# UmnitsaRGB.net
KiCad netlist of a schematic drawn in EAGLE
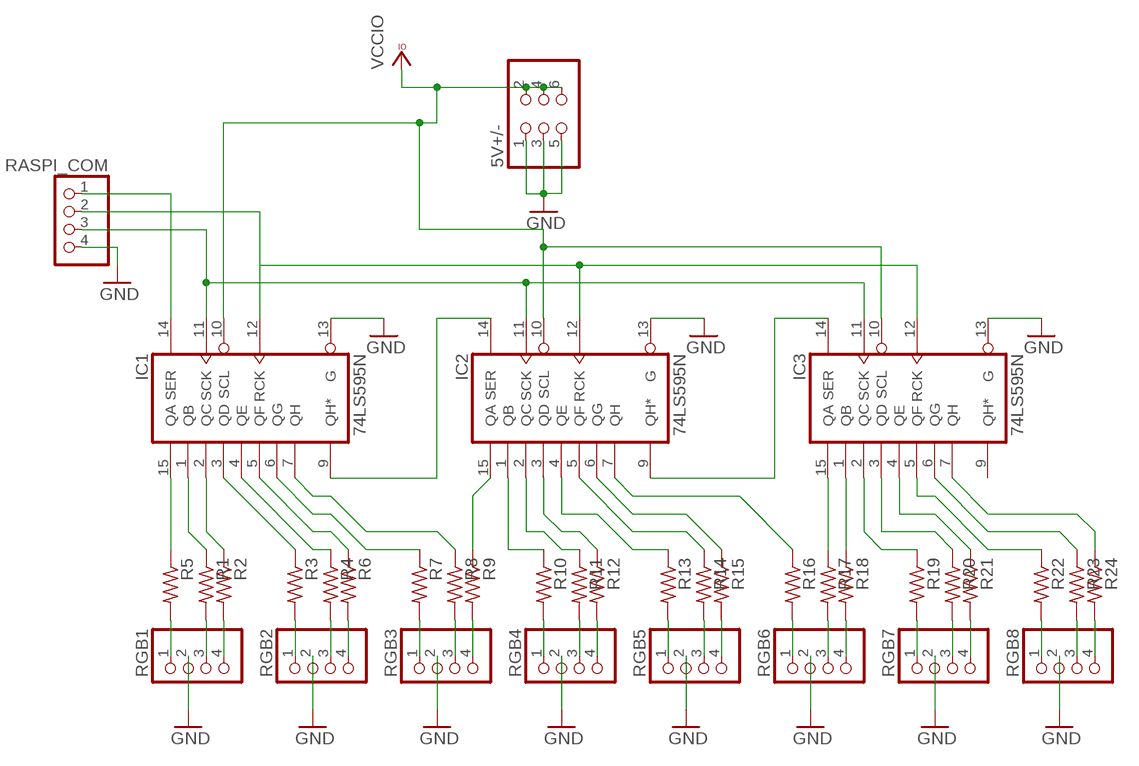
[diagram p0: schematic, sheet 1]

(export (version "E")
  (design (tool "Eeschema 10.0.6"))
  (components
    (comp (ref "5V+/-")
      (value "PINHD-2X3")
      (footprint "eagle-import:2X03")
      (libsource (lib "eagle-import") (part "PINHD-2X3"))
    )
    (comp (ref "IC1")
      (value "74LS595N")
      (footprint "eagle-import:DIL16")
      (libsource (lib "eagle-import") (part "74595NLS"))
    )
    (comp (ref "IC2")
      (value "74LS595N")
      (footprint "eagle-import:DIL16")
      (libsource (lib "eagle-import") (part "74595NLS"))
    )
    (comp (ref "IC3")
      (value "74LS595N")
      (footprint "eagle-import:DIL16")
      (libsource (lib "eagle-import") (part "74595NLS"))
    )
    (comp (ref "R1")
      (value "R-US_0204/7")
      (footprint "eagle-import:0204_7")
      (libsource (lib "eagle-import") (part "R-US_0204/7"))
    )
    (comp (ref "R2")
      (value "R-US_0204/7")
      (footprint "eagle-import:0204_7")
      (libsource (lib "eagle-import") (part "R-US_0204/7"))
    )
    (comp (ref "R3")
      (value "R-US_0204/7")
      (footprint "eagle-import:0204_7")
      (libsource (lib "eagle-import") (part "R-US_0204/7"))
    )
    (comp (ref "R4")
      (value "R-US_0204/7")
      (footprint "eagle-import:0204_7")
      (libsource (lib "eagle-import") (part "R-US_0204/7"))
    )
    (comp (ref "R5")
      (value "R-US_0204/7")
      (footprint "eagle-import:0204_7")
      (libsource (lib "eagle-import") (part "R-US_0204/7"))
    )
    (comp (ref "R6")
      (value "R-US_0204/7")
      (footprint "eagle-import:0204_7")
      (libsource (lib "eagle-import") (part "R-US_0204/7"))
    )
    (comp (ref "R7")
      (value "R-US_0204/7")
      (footprint "eagle-import:0204_7")
      (libsource (lib "eagle-import") (part "R-US_0204/7"))
    )
    (comp (ref "R8")
      (value "R-US_0204/7")
      (footprint "eagle-import:0204_7")
      (libsource (lib "eagle-import") (part "R-US_0204/7"))
    )
    (comp (ref "R9")
      (value "R-US_0204/7")
      (footprint "eagle-import:0204_7")
      (libsource (lib "eagle-import") (part "R-US_0204/7"))
    )
    (comp (ref "R10")
      (value "R-US_0204/7")
      (footprint "eagle-import:0204_7")
      (libsource (lib "eagle-import") (part "R-US_0204/7"))
    )
    (comp (ref "R11")
      (value "R-US_0204/7")
      (footprint "eagle-import:0204_7")
      (libsource (lib "eagle-import") (part "R-US_0204/7"))
    )
    (comp (ref "R12")
      (value "R-US_0204/7")
      (footprint "eagle-import:0204_7")
      (libsource (lib "eagle-import") (part "R-US_0204/7"))
    )
    (comp (ref "R13")
      (value "R-US_0204/7")
      (footprint "eagle-import:0204_7")
      (libsource (lib "eagle-import") (part "R-US_0204/7"))
    )
    (comp (ref "R14")
      (value "R-US_0204/7")
      (footprint "eagle-import:0204_7")
      (libsource (lib "eagle-import") (part "R-US_0204/7"))
    )
    (comp (ref "R15")
      (value "R-US_0204/7")
      (footprint "eagle-import:0204_7")
      (libsource (lib "eagle-import") (part "R-US_0204/7"))
    )
    (comp (ref "R16")
      (value "R-US_0204/7")
      (footprint "eagle-import:0204_7")
      (libsource (lib "eagle-import") (part "R-US_0204/7"))
    )
    (comp (ref "R17")
      (value "R-US_0204/7")
      (footprint "eagle-import:0204_7")
      (libsource (lib "eagle-import") (part "R-US_0204/7"))
    )
    (comp (ref "R18")
      (value "R-US_0204/7")
      (footprint "eagle-import:0204_7")
      (libsource (lib "eagle-import") (part "R-US_0204/7"))
    )
    (comp (ref "R19")
      (value "R-US_0204/7")
      (footprint "eagle-import:0204_7")
      (libsource (lib "eagle-import") (part "R-US_0204/7"))
    )
    (comp (ref "R20")
      (value "R-US_0204/7")
      (footprint "eagle-import:0204_7")
      (libsource (lib "eagle-import") (part "R-US_0204/7"))
    )
    (comp (ref "R21")
      (value "R-US_0204/7")
      (footprint "eagle-import:0204_7")
      (libsource (lib "eagle-import") (part "R-US_0204/7"))
    )
    (comp (ref "R22")
      (value "R-US_0204/7")
      (footprint "eagle-import:0204_7")
      (libsource (lib "eagle-import") (part "R-US_0204/7"))
    )
    (comp (ref "R23")
      (value "R-US_0204/7")
      (footprint "eagle-import:0204_7")
      (libsource (lib "eagle-import") (part "R-US_0204/7"))
    )
    (comp (ref "R24")
      (value "R-US_0204/7")
      (footprint "eagle-import:0204_7")
      (libsource (lib "eagle-import") (part "R-US_0204/7"))
    )
    (comp (ref "RASPI_COM")
      (value "PINHD-1X4")
      (footprint "eagle-import:1X04")
      (libsource (lib "eagle-import") (part "PINHD-1X4"))
    )
    (comp (ref "RGB1")
      (value "PINHD-1X4")
      (footprint "eagle-import:1X04")
      (libsource (lib "eagle-import") (part "PINHD-1X4"))
    )
    (comp (ref "RGB2")
      (value "PINHD-1X4")
      (footprint "eagle-import:1X04")
      (libsource (lib "eagle-import") (part "PINHD-1X4"))
    )
    (comp (ref "RGB3")
      (value "PINHD-1X4")
      (footprint "eagle-import:1X04")
      (libsource (lib "eagle-import") (part "PINHD-1X4"))
    )
    (comp (ref "RGB4")
      (value "PINHD-1X4")
      (footprint "eagle-import:1X04")
      (libsource (lib "eagle-import") (part "PINHD-1X4"))
    )
    (comp (ref "RGB5")
      (value "PINHD-1X4")
      (footprint "eagle-import:1X04")
      (libsource (lib "eagle-import") (part "PINHD-1X4"))
    )
    (comp (ref "RGB6")
      (value "PINHD-1X4")
      (footprint "eagle-import:1X04")
      (libsource (lib "eagle-import") (part "PINHD-1X4"))
    )
    (comp (ref "RGB7")
      (value "PINHD-1X4")
      (footprint "eagle-import:1X04")
      (libsource (lib "eagle-import") (part "PINHD-1X4"))
    )
    (comp (ref "RGB8")
      (value "PINHD-1X4")
      (footprint "eagle-import:1X04")
      (libsource (lib "eagle-import") (part "PINHD-1X4"))
    )
  )
  (nets
    (net (code "1") (name "GND") (class "Default")
      (node (ref "5V+/-") (pin "1") (pinfunction "1_1") (pintype "passive"))
      (node (ref "5V+/-") (pin "3") (pinfunction "3_3") (pintype "passive"))
      (node (ref "5V+/-") (pin "5") (pinfunction "5_5") (pintype "passive"))
      (node (ref "IC1") (pin "13") (pinfunction "G_13") (pintype "input"))
      (node (ref "IC2") (pin "13") (pinfunction "G_13") (pintype "input"))
      (node (ref "IC3") (pin "13") (pinfunction "G_13") (pintype "input"))
      (node (ref "RASPI_COM") (pin "4") (pinfunction "4_4") (pintype "passive"))
      (node (ref "RGB1") (pin "2") (pinfunction "2_2") (pintype "passive"))
      (node (ref "RGB2") (pin "2") (pinfunction "2_2") (pintype "passive"))
      (node (ref "RGB3") (pin "2") (pinfunction "2_2") (pintype "passive"))
      (node (ref "RGB4") (pin "2") (pinfunction "2_2") (pintype "passive"))
      (node (ref "RGB5") (pin "2") (pinfunction "2_2") (pintype "passive"))
      (node (ref "RGB6") (pin "2") (pinfunction "2_2") (pintype "passive"))
      (node (ref "RGB7") (pin "2") (pinfunction "2_2") (pintype "passive"))
      (node (ref "RGB8") (pin "2") (pinfunction "2_2") (pintype "passive"))
    )
    (net (code "2") (name "Net-(IC1A-QA)") (class "Default")
      (node (ref "IC1") (pin "15") (pinfunction "QA_15") (pintype "tri_state"))
      (node (ref "R5") (pin "1") (pinfunction "1_1") (pintype "passive"))
    )
    (net (code "3") (name "Net-(IC1A-QB)") (class "Default")
      (node (ref "IC1") (pin "1") (pinfunction "QB_1") (pintype "tri_state"))
      (node (ref "R1") (pin "1") (pinfunction "1_1") (pintype "passive"))
    )
    (net (code "4") (name "Net-(IC1A-QC)") (class "Default")
      (node (ref "IC1") (pin "2") (pinfunction "QC_2") (pintype "tri_state"))
      (node (ref "R2") (pin "1") (pinfunction "1_1") (pintype "passive"))
    )
    (net (code "5") (name "Net-(IC1A-QD)") (class "Default")
      (node (ref "IC1") (pin "3") (pinfunction "QD_3") (pintype "tri_state"))
      (node (ref "R3") (pin "1") (pinfunction "1_1") (pintype "passive"))
    )
    (net (code "6") (name "Net-(IC1A-QE)") (class "Default")
      (node (ref "IC1") (pin "4") (pinfunction "QE_4") (pintype "tri_state"))
      (node (ref "R4") (pin "1") (pinfunction "1_1") (pintype "passive"))
    )
    (net (code "7") (name "Net-(IC1A-QF)") (class "Default")
      (node (ref "IC1") (pin "5") (pinfunction "QF_5") (pintype "tri_state"))
      (node (ref "R6") (pin "1") (pinfunction "1_1") (pintype "passive"))
    )
    (net (code "8") (name "Net-(IC1A-QG)") (class "Default")
      (node (ref "IC1") (pin "6") (pinfunction "QG_6") (pintype "tri_state"))
      (node (ref "R7") (pin "1") (pinfunction "1_1") (pintype "passive"))
    )
    (net (code "9") (name "Net-(IC1A-QH)") (class "Default")
      (node (ref "IC1") (pin "7") (pinfunction "QH_7") (pintype "tri_state"))
      (node (ref "R8") (pin "1") (pinfunction "1_1") (pintype "passive"))
    )
    (net (code "10") (name "Net-(IC1A-QH*)") (class "Default")
      (node (ref "IC1") (pin "9") (pinfunction "QH*_9") (pintype "tri_state"))
      (node (ref "IC2") (pin "14") (pinfunction "SER_14") (pintype "input"))
    )
    (net (code "11") (name "Net-(IC1A-RCK)") (class "Default")
      (node (ref "IC1") (pin "12") (pinfunction "RCK_12") (pintype "input"))
      (node (ref "IC2") (pin "12") (pinfunction "RCK_12") (pintype "input"))
      (node (ref "IC3") (pin "12") (pinfunction "RCK_12") (pintype "input"))
      (node (ref "RASPI_COM") (pin "2") (pinfunction "2_2") (pintype "passive"))
    )
    (net (code "12") (name "Net-(IC1A-SCK)") (class "Default")
      (node (ref "IC1") (pin "11") (pinfunction "SCK_11") (pintype "input"))
      (node (ref "IC2") (pin "11") (pinfunction "SCK_11") (pintype "input"))
      (node (ref "IC3") (pin "11") (pinfunction "SCK_11") (pintype "input"))
      (node (ref "RASPI_COM") (pin "3") (pinfunction "3_3") (pintype "passive"))
    )
    (net (code "13") (name "Net-(IC1A-SER)") (class "Default")
      (node (ref "IC1") (pin "14") (pinfunction "SER_14") (pintype "input"))
      (node (ref "RASPI_COM") (pin "1") (pinfunction "1_1") (pintype "passive"))
    )
    (net (code "14") (name "Net-(IC2A-QA)") (class "Default")
      (node (ref "IC2") (pin "15") (pinfunction "QA_15") (pintype "tri_state"))
      (node (ref "R9") (pin "1") (pinfunction "1_1") (pintype "passive"))
    )
    (net (code "15") (name "Net-(IC2A-QB)") (class "Default")
      (node (ref "IC2") (pin "1") (pinfunction "QB_1") (pintype "tri_state"))
      (node (ref "R10") (pin "1") (pinfunction "1_1") (pintype "passive"))
    )
    (net (code "16") (name "Net-(IC2A-QC)") (class "Default")
      (node (ref "IC2") (pin "2") (pinfunction "QC_2") (pintype "tri_state"))
      (node (ref "R11") (pin "1") (pinfunction "1_1") (pintype "passive"))
    )
    (net (code "17") (name "Net-(IC2A-QD)") (class "Default")
      (node (ref "IC2") (pin "3") (pinfunction "QD_3") (pintype "tri_state"))
      (node (ref "R12") (pin "1") (pinfunction "1_1") (pintype "passive"))
    )
    (net (code "18") (name "Net-(IC2A-QE)") (class "Default")
      (node (ref "IC2") (pin "4") (pinfunction "QE_4") (pintype "tri_state"))
      (node (ref "R13") (pin "1") (pinfunction "1_1") (pintype "passive"))
    )
    (net (code "19") (name "Net-(IC2A-QF)") (class "Default")
      (node (ref "IC2") (pin "5") (pinfunction "QF_5") (pintype "tri_state"))
      (node (ref "R14") (pin "1") (pinfunction "1_1") (pintype "passive"))
    )
    (net (code "20") (name "Net-(IC2A-QG)") (class "Default")
      (node (ref "IC2") (pin "6") (pinfunction "QG_6") (pintype "tri_state"))
      (node (ref "R15") (pin "1") (pinfunction "1_1") (pintype "passive"))
    )
    (net (code "21") (name "Net-(IC2A-QH)") (class "Default")
      (node (ref "IC2") (pin "7") (pinfunction "QH_7") (pintype "tri_state"))
      (node (ref "R16") (pin "1") (pinfunction "1_1") (pintype "passive"))
    )
    (net (code "22") (name "Net-(IC2A-QH*)") (class "Default")
      (node (ref "IC2") (pin "9") (pinfunction "QH*_9") (pintype "tri_state"))
      (node (ref "IC3") (pin "14") (pinfunction "SER_14") (pintype "input"))
    )
    (net (code "23") (name "Net-(IC3A-QA)") (class "Default")
      (node (ref "IC3") (pin "15") (pinfunction "QA_15") (pintype "tri_state"))
      (node (ref "R17") (pin "1") (pinfunction "1_1") (pintype "passive"))
    )
    (net (code "24") (name "Net-(IC3A-QB)") (class "Default")
      (node (ref "IC3") (pin "1") (pinfunction "QB_1") (pintype "tri_state"))
      (node (ref "R18") (pin "1") (pinfunction "1_1") (pintype "passive"))
    )
    (net (code "25") (name "Net-(IC3A-QC)") (class "Default")
      (node (ref "IC3") (pin "2") (pinfunction "QC_2") (pintype "tri_state"))
      (node (ref "R19") (pin "1") (pinfunction "1_1") (pintype "passive"))
    )
    (net (code "26") (name "Net-(IC3A-QD)") (class "Default")
      (node (ref "IC3") (pin "3") (pinfunction "QD_3") (pintype "tri_state"))
      (node (ref "R20") (pin "1") (pinfunction "1_1") (pintype "passive"))
    )
    (net (code "27") (name "Net-(IC3A-QE)") (class "Default")
      (node (ref "IC3") (pin "4") (pinfunction "QE_4") (pintype "tri_state"))
      (node (ref "R21") (pin "1") (pinfunction "1_1") (pintype "passive"))
    )
    (net (code "28") (name "Net-(IC3A-QF)") (class "Default")
      (node (ref "IC3") (pin "5") (pinfunction "QF_5") (pintype "tri_state"))
      (node (ref "R22") (pin "1") (pinfunction "1_1") (pintype "passive"))
    )
    (net (code "29") (name "Net-(IC3A-QG)") (class "Default")
      (node (ref "IC3") (pin "6") (pinfunction "QG_6") (pintype "tri_state"))
      (node (ref "R23") (pin "1") (pinfunction "1_1") (pintype "passive"))
    )
    (net (code "30") (name "Net-(IC3A-QH)") (class "Default")
      (node (ref "IC3") (pin "7") (pinfunction "QH_7") (pintype "tri_state"))
      (node (ref "R24") (pin "1") (pinfunction "1_1") (pintype "passive"))
    )
    (net (code "31") (name "Net-(R1-Pad2)") (class "Default")
      (node (ref "R1") (pin "2") (pinfunction "2_2") (pintype "passive"))
      (node (ref "RGB1") (pin "3") (pinfunction "3_3") (pintype "passive"))
    )
    (net (code "32") (name "Net-(R2-Pad2)") (class "Default")
      (node (ref "R2") (pin "2") (pinfunction "2_2") (pintype "passive"))
      (node (ref "RGB1") (pin "4") (pinfunction "4_4") (pintype "passive"))
    )
    (net (code "33") (name "Net-(R3-Pad2)") (class "Default")
      (node (ref "R3") (pin "2") (pinfunction "2_2") (pintype "passive"))
      (node (ref "RGB2") (pin "1") (pinfunction "1_1") (pintype "passive"))
    )
    (net (code "34") (name "Net-(R4-Pad2)") (class "Default")
      (node (ref "R4") (pin "2") (pinfunction "2_2") (pintype "passive"))
      (node (ref "RGB2") (pin "3") (pinfunction "3_3") (pintype "passive"))
    )
    (net (code "35") (name "Net-(R5-Pad2)") (class "Default")
      (node (ref "R5") (pin "2") (pinfunction "2_2") (pintype "passive"))
      (node (ref "RGB1") (pin "1") (pinfunction "1_1") (pintype "passive"))
    )
    (net (code "36") (name "Net-(R6-Pad2)") (class "Default")
      (node (ref "R6") (pin "2") (pinfunction "2_2") (pintype "passive"))
      (node (ref "RGB2") (pin "4") (pinfunction "4_4") (pintype "passive"))
    )
    (net (code "37") (name "Net-(R7-Pad2)") (class "Default")
      (node (ref "R7") (pin "2") (pinfunction "2_2") (pintype "passive"))
      (node (ref "RGB3") (pin "1") (pinfunction "1_1") (pintype "passive"))
    )
    (net (code "38") (name "Net-(R8-Pad2)") (class "Default")
      (node (ref "R8") (pin "2") (pinfunction "2_2") (pintype "passive"))
      (node (ref "RGB3") (pin "3") (pinfunction "3_3") (pintype "passive"))
    )
    (net (code "39") (name "Net-(R9-Pad2)") (class "Default")
      (node (ref "R9") (pin "2") (pinfunction "2_2") (pintype "passive"))
      (node (ref "RGB3") (pin "4") (pinfunction "4_4") (pintype "passive"))
    )
    (net (code "40") (name "Net-(R10-Pad2)") (class "Default")
      (node (ref "R10") (pin "2") (pinfunction "2_2") (pintype "passive"))
      (node (ref "RGB4") (pin "1") (pinfunction "1_1") (pintype "passive"))
    )
    (net (code "41") (name "Net-(R11-Pad2)") (class "Default")
      (node (ref "R11") (pin "2") (pinfunction "2_2") (pintype "passive"))
      (node (ref "RGB4") (pin "3") (pinfunction "3_3") (pintype "passive"))
    )
    (net (code "42") (name "Net-(R12-Pad2)") (class "Default")
      (node (ref "R12") (pin "2") (pinfunction "2_2") (pintype "passive"))
      (node (ref "RGB4") (pin "4") (pinfunction "4_4") (pintype "passive"))
    )
    (net (code "43") (name "Net-(R13-Pad2)") (class "Default")
      (node (ref "R13") (pin "2") (pinfunction "2_2") (pintype "passive"))
      (node (ref "RGB5") (pin "1") (pinfunction "1_1") (pintype "passive"))
    )
    (net (code "44") (name "Net-(R14-Pad2)") (class "Default")
      (node (ref "R14") (pin "2") (pinfunction "2_2") (pintype "passive"))
      (node (ref "RGB5") (pin "3") (pinfunction "3_3") (pintype "passive"))
    )
    (net (code "45") (name "Net-(R15-Pad2)") (class "Default")
      (node (ref "R15") (pin "2") (pinfunction "2_2") (pintype "passive"))
      (node (ref "RGB5") (pin "4") (pinfunction "4_4") (pintype "passive"))
    )
    (net (code "46") (name "Net-(R16-Pad2)") (class "Default")
      (node (ref "R16") (pin "2") (pinfunction "2_2") (pintype "passive"))
      (node (ref "RGB6") (pin "1") (pinfunction "1_1") (pintype "passive"))
    )
    (net (code "47") (name "Net-(R17-Pad2)") (class "Default")
      (node (ref "R17") (pin "2") (pinfunction "2_2") (pintype "passive"))
      (node (ref "RGB6") (pin "3") (pinfunction "3_3") (pintype "passive"))
    )
    (net (code "48") (name "Net-(R18-Pad2)") (class "Default")
      (node (ref "R18") (pin "2") (pinfunction "2_2") (pintype "passive"))
      (node (ref "RGB6") (pin "4") (pinfunction "4_4") (pintype "passive"))
    )
    (net (code "49") (name "Net-(R19-Pad2)") (class "Default")
      (node (ref "R19") (pin "2") (pinfunction "2_2") (pintype "passive"))
      (node (ref "RGB7") (pin "1") (pinfunction "1_1") (pintype "passive"))
    )
    (net (code "50") (name "Net-(R20-Pad2)") (class "Default")
      (node (ref "R20") (pin "2") (pinfunction "2_2") (pintype "passive"))
      (node (ref "RGB7") (pin "3") (pinfunction "3_3") (pintype "passive"))
    )
    (net (code "51") (name "Net-(R21-Pad2)") (class "Default")
      (node (ref "R21") (pin "2") (pinfunction "2_2") (pintype "passive"))
      (node (ref "RGB7") (pin "4") (pinfunction "4_4") (pintype "passive"))
    )
    (net (code "52") (name "Net-(R22-Pad2)") (class "Default")
      (node (ref "R22") (pin "2") (pinfunction "2_2") (pintype "passive"))
      (node (ref "RGB8") (pin "1") (pinfunction "1_1") (pintype "passive"))
    )
    (net (code "53") (name "Net-(R23-Pad2)") (class "Default")
      (node (ref "R23") (pin "2") (pinfunction "2_2") (pintype "passive"))
      (node (ref "RGB8") (pin "3") (pinfunction "3_3") (pintype "passive"))
    )
    (net (code "54") (name "Net-(R24-Pad2)") (class "Default")
      (node (ref "R24") (pin "2") (pinfunction "2_2") (pintype "passive"))
      (node (ref "RGB8") (pin "4") (pinfunction "4_4") (pintype "passive"))
    )
    (net (code "55") (name "VCCIO") (class "Default")
      (node (ref "5V+/-") (pin "2") (pinfunction "2_2") (pintype "passive"))
      (node (ref "5V+/-") (pin "4") (pinfunction "4_4") (pintype "passive"))
      (node (ref "5V+/-") (pin "6") (pinfunction "6_6") (pintype "passive"))
      (node (ref "IC1") (pin "10") (pinfunction "SCL_10") (pintype "input"))
      (node (ref "IC2") (pin "10") (pinfunction "SCL_10") (pintype "input"))
      (node (ref "IC3") (pin "10") (pinfunction "SCL_10") (pintype "input"))
    )
    (net (code "56") (name "unconnected-(IC3A-QH*-Pad9)") (class "Default")
      (node (ref "IC3") (pin "9") (pinfunction "QH*_9") (pintype "tri_state"))
    )
  )
)
